# e.net
KiCad netlist of a schematic drawn in EasyEDA
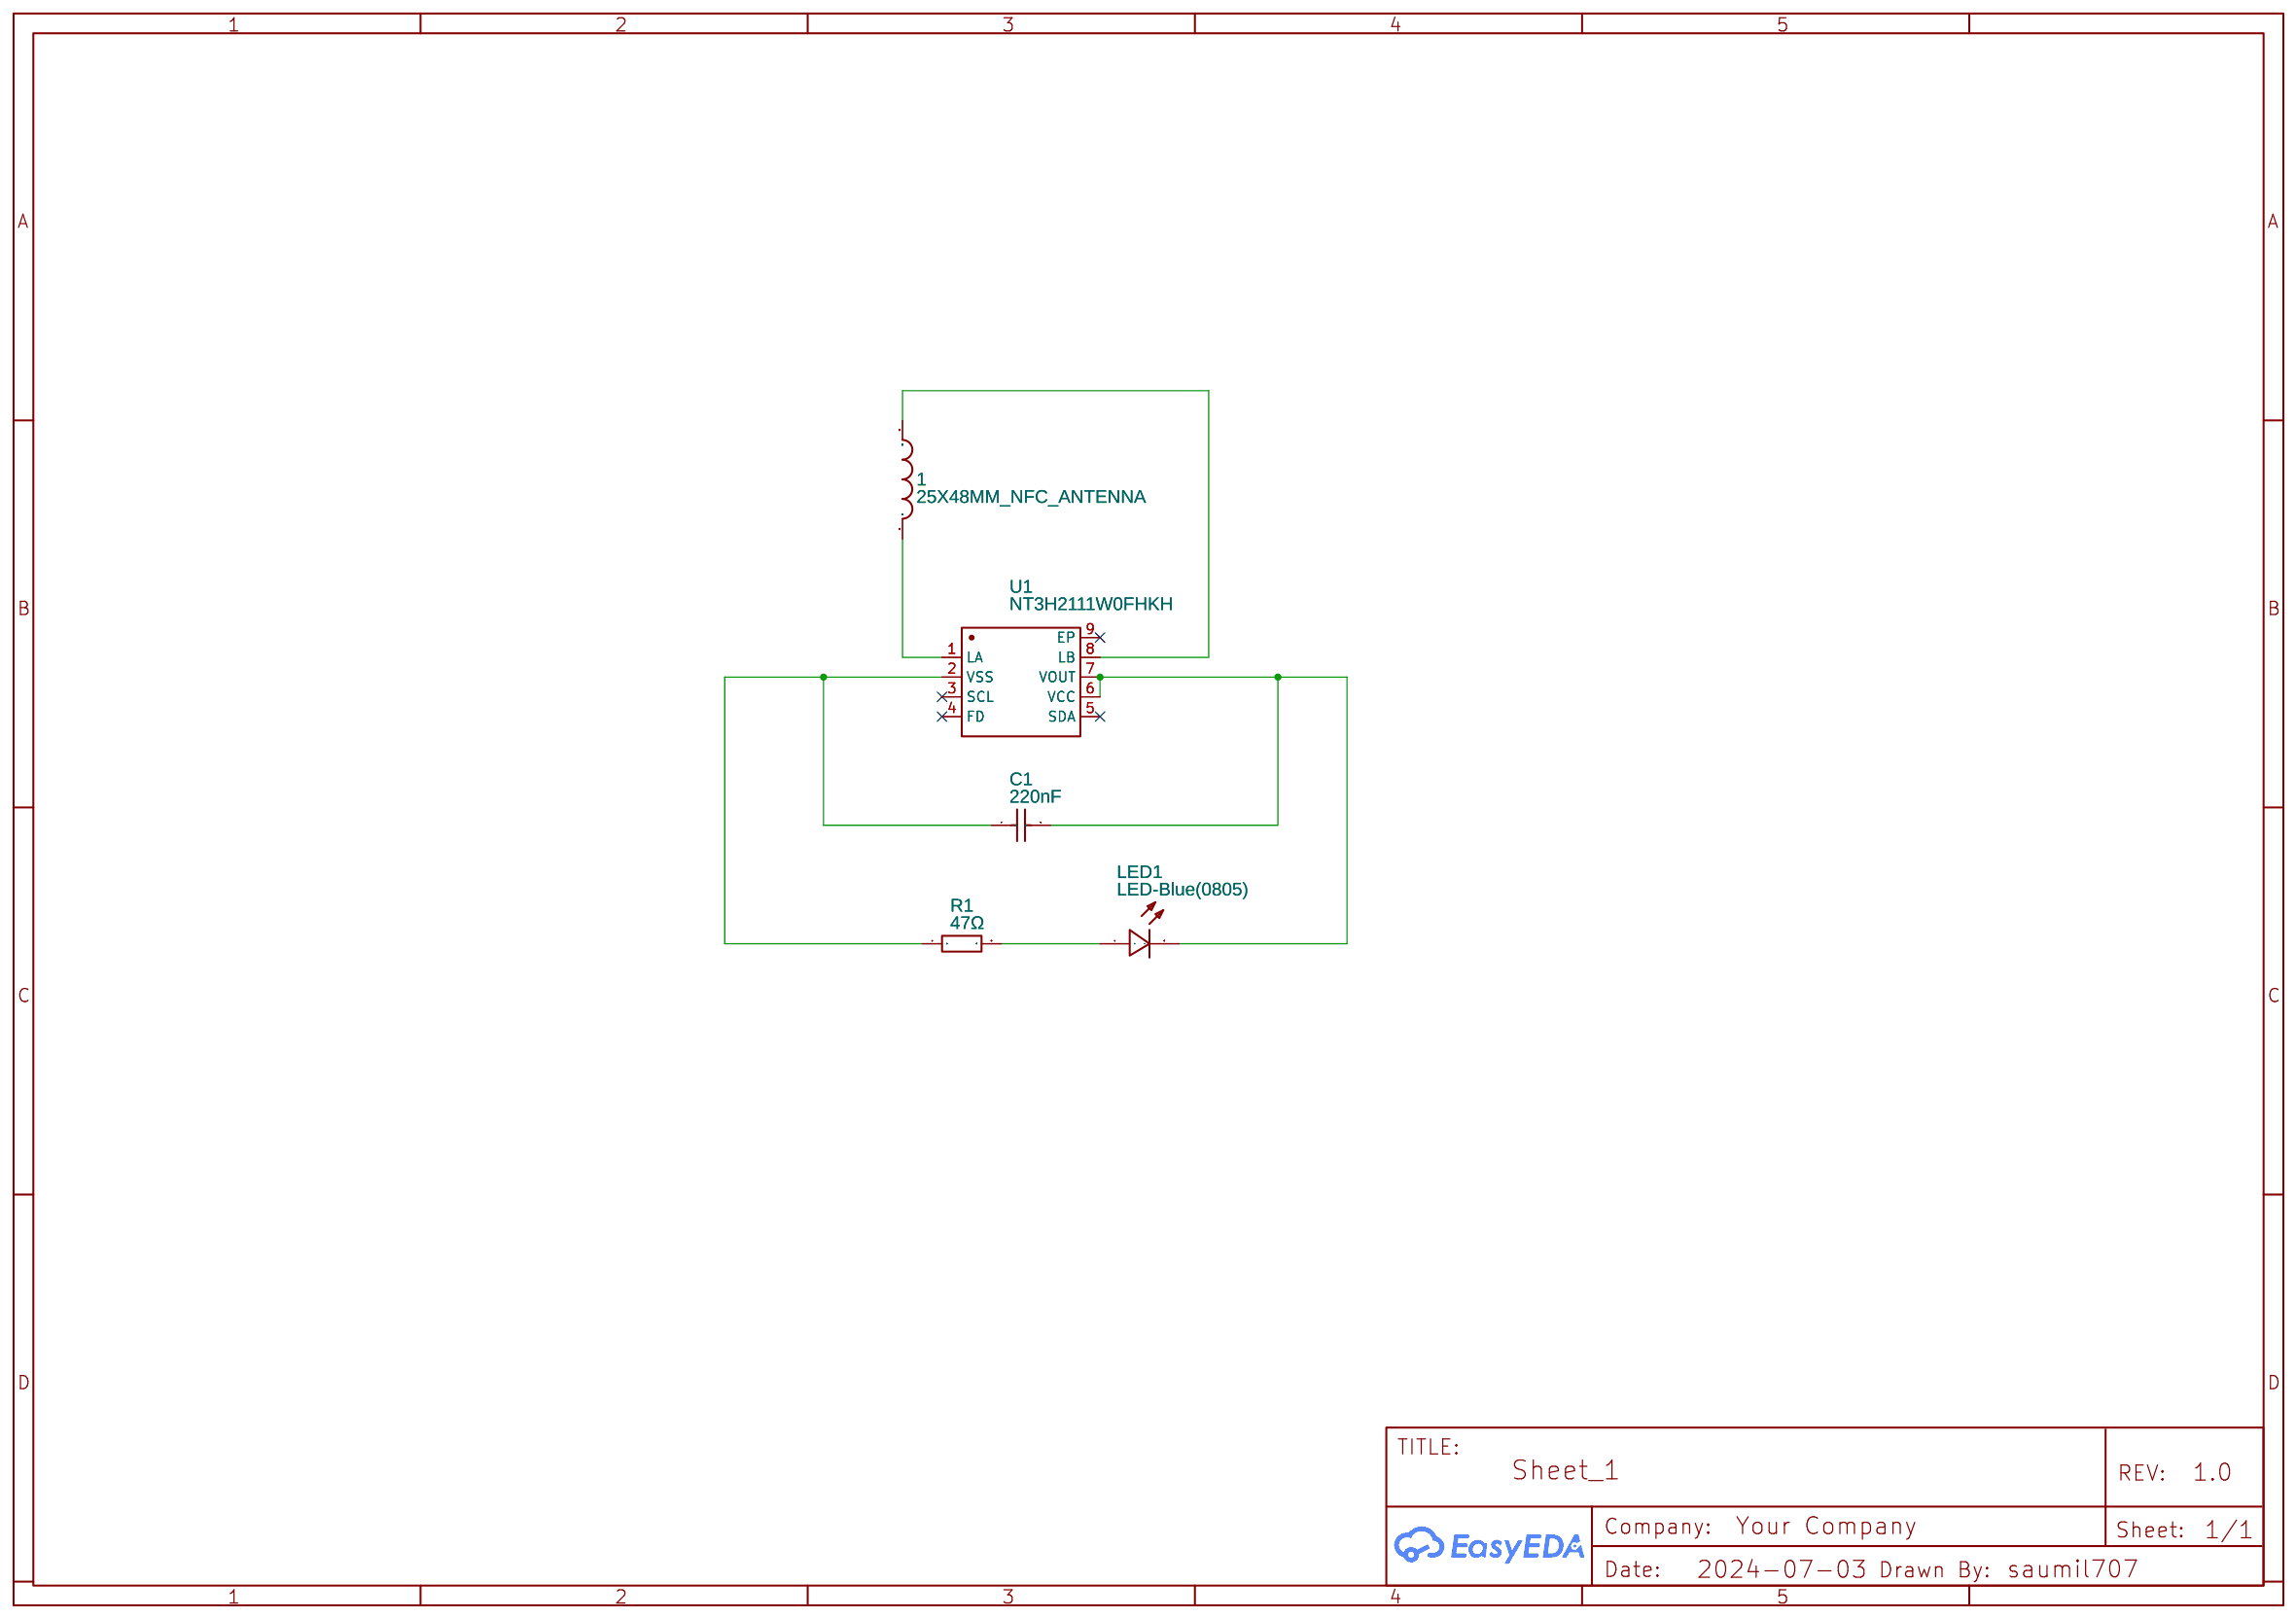
[diagram p0: schematic sheet]

(export (version "E")
  (design (tool "Eeschema 10.0.6"))
  (components
    (comp (ref "1") (value "25X48MM_NFC_ANTENNA") (libsource (lib "") (part "25X48MM_NFC_ANTENNA")))
    (comp (ref "C1")
      (value "220nF")
      (fields
        (field (name "Manufacturer Part") "CL10B224KA8NNNC")
        (field (name "Manufacturer") "SAMSUNG(三星)")
      )
      (libsource (lib "") (part "CL10B224KA8NNNC"))
    )
    (comp (ref "LED1")
      (value "LED-Blue(0805)")
      (fields
        (field (name "Manufacturer Part") "17-21/BHC-XL2M2TY/3T")
        (field (name "Manufacturer") "Everlight Elec")
      )
      (libsource (lib "") (part "LED-Blue(0805)"))
    )
    (comp (ref "R1")
      (value "47Ω")
      (fields
        (field (name "Manufacturer Part") "0603WAF470JT5E")
        (field (name "Manufacturer") "UNI-ROYAL(厚声)")
      )
      (libsource (lib "") (part "0603WAF470JT5E"))
    )
    (comp (ref "U1")
      (value "NT3H2111W0FHKH")
      (fields (field (name "Manufacturer") "NXP(恩智浦)"))
      (libsource (lib "") (part "NT3H2111W0FHKH"))
    )
  )
  (nets
    (net (code "1") (name "Net-(LED1-+)") (class "Default")
      (node (ref "LED1") (pin "1") (pinfunction "+_1") (pintype "unspecified"))
      (node (ref "R1") (pin "2") (pinfunction "2_2") (pintype "input"))
    )
    (net (code "2") (name "Net-(LED1--)") (class "Default")
      (node (ref "C1") (pin "2") (pinfunction "2_2") (pintype "input"))
      (node (ref "LED1") (pin "2") (pinfunction "-_2") (pintype "unspecified"))
      (node (ref "U1") (pin "6") (pinfunction "VCC_6") (pintype "unspecified"))
      (node (ref "U1") (pin "7") (pinfunction "VOUT_7") (pintype "unspecified"))
    )
    (net (code "3") (name "Net-(U1-LA)") (class "Default")
      (node (ref "1") (pin "P$2") (pinfunction "P$2_P$2") (pintype "bidirectional"))
      (node (ref "U1") (pin "1") (pinfunction "LA_1") (pintype "unspecified"))
    )
    (net (code "4") (name "Net-(U1-LB)") (class "Default")
      (node (ref "1") (pin "P$1") (pinfunction "P$1_P$1") (pintype "bidirectional"))
      (node (ref "U1") (pin "8") (pinfunction "LB_8") (pintype "unspecified"))
    )
    (net (code "5") (name "Net-(U1-VSS)") (class "Default")
      (node (ref "C1") (pin "1") (pinfunction "1_1") (pintype "input"))
      (node (ref "R1") (pin "1") (pinfunction "1_1") (pintype "input"))
      (node (ref "U1") (pin "2") (pinfunction "VSS_2") (pintype "unspecified"))
    )
    (net (code "6") (name "unconnected-(U1-EP-Pad9)") (class "Default")
      (node (ref "U1") (pin "9") (pinfunction "EP_9") (pintype "unspecified+no_connect"))
    )
    (net (code "7") (name "unconnected-(U1-FD-Pad4)") (class "Default")
      (node (ref "U1") (pin "4") (pinfunction "FD_4") (pintype "unspecified+no_connect"))
    )
    (net (code "8") (name "unconnected-(U1-SCL-Pad3)") (class "Default")
      (node (ref "U1") (pin "3") (pinfunction "SCL_3") (pintype "unspecified+no_connect"))
    )
    (net (code "9") (name "unconnected-(U1-SDA-Pad5)") (class "Default")
      (node (ref "U1") (pin "5") (pinfunction "SDA_5") (pintype "unspecified+no_connect"))
    )
  )
)
